# brakeBoard.net
KiCad netlist of a schematic drawn in EAGLE
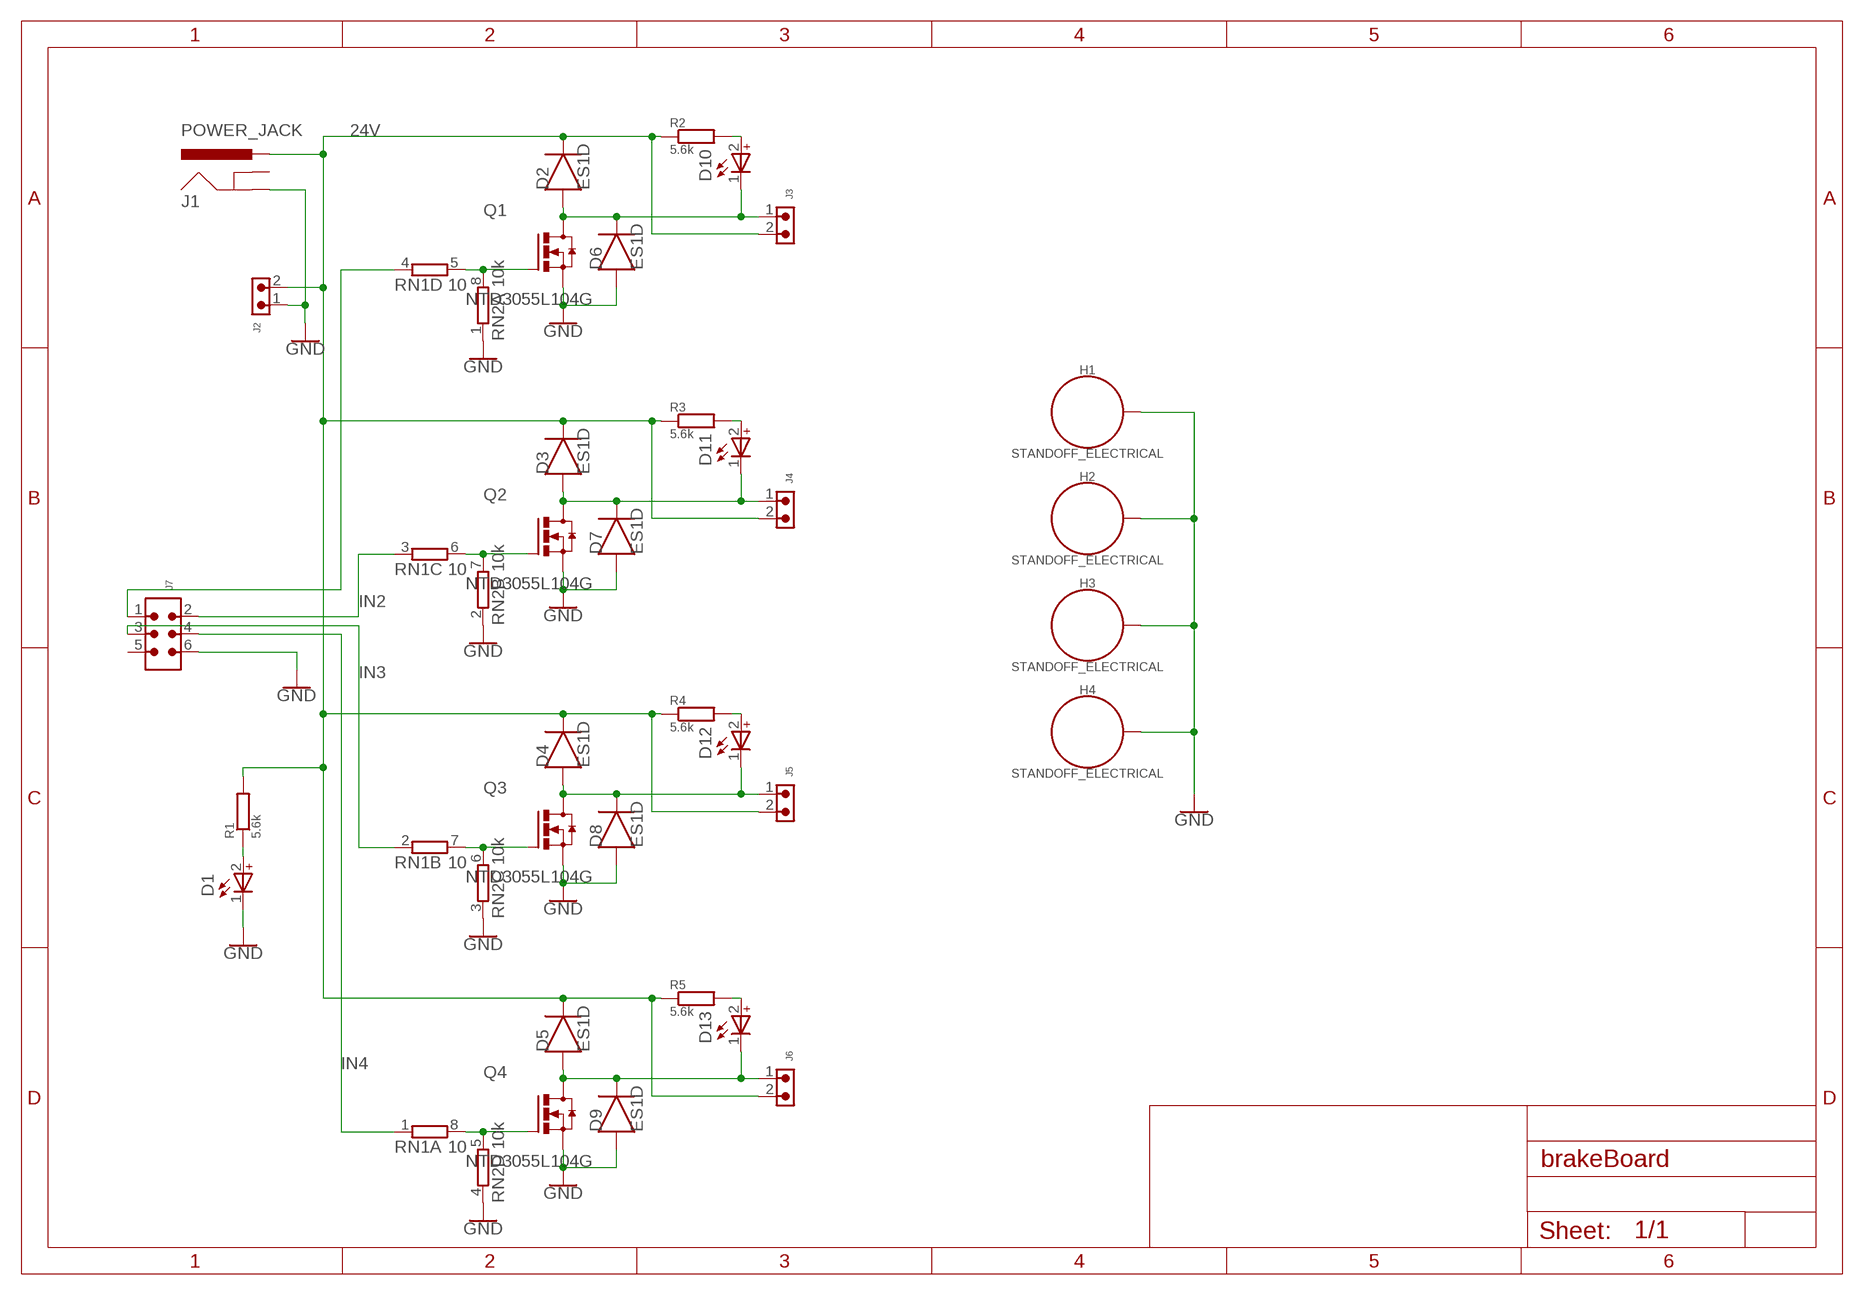
[diagram p0: schematic, sheet 1]

(export (version "E")
  (design (tool "Eeschema 10.0.6"))
  (components
    (comp (ref "D1")
      (value "WL-SMCD_0603_150060GS55040")
      (footprint "eagle-import:WL-SMCD_0603")
      (libsource (lib "eagle-import") (part "WL-SMCD_0603_150060GS55040"))
    )
    (comp (ref "D2")
      (value "ES1D")
      (footprint "eagle-import:DIOM5226X290N")
      (fields (field (name "MANUFACTURER") "ON Semiconductor "))
      (libsource (lib "eagle-import") (part "DIODE__SMAES1D"))
    )
    (comp (ref "D3")
      (value "ES1D")
      (footprint "eagle-import:DIOM5226X290N")
      (fields (field (name "MANUFACTURER") "ON Semiconductor "))
      (libsource (lib "eagle-import") (part "DIODE__SMAES1D"))
    )
    (comp (ref "D4")
      (value "ES1D")
      (footprint "eagle-import:DIOM5226X290N")
      (fields (field (name "MANUFACTURER") "ON Semiconductor "))
      (libsource (lib "eagle-import") (part "DIODE__SMAES1D"))
    )
    (comp (ref "D5")
      (value "ES1D")
      (footprint "eagle-import:DIOM5226X290N")
      (fields (field (name "MANUFACTURER") "ON Semiconductor "))
      (libsource (lib "eagle-import") (part "DIODE__SMAES1D"))
    )
    (comp (ref "D6")
      (value "ES1D")
      (footprint "eagle-import:DIOM5226X290N")
      (fields (field (name "MANUFACTURER") "ON Semiconductor "))
      (libsource (lib "eagle-import") (part "DIODE__SMAES1D"))
    )
    (comp (ref "D7")
      (value "ES1D")
      (footprint "eagle-import:DIOM5226X290N")
      (fields (field (name "MANUFACTURER") "ON Semiconductor "))
      (libsource (lib "eagle-import") (part "DIODE__SMAES1D"))
    )
    (comp (ref "D8")
      (value "ES1D")
      (footprint "eagle-import:DIOM5226X290N")
      (fields (field (name "MANUFACTURER") "ON Semiconductor "))
      (libsource (lib "eagle-import") (part "DIODE__SMAES1D"))
    )
    (comp (ref "D9")
      (value "ES1D")
      (footprint "eagle-import:DIOM5226X290N")
      (fields (field (name "MANUFACTURER") "ON Semiconductor "))
      (libsource (lib "eagle-import") (part "DIODE__SMAES1D"))
    )
    (comp (ref "D10")
      (value "WL-SMCD_0603_150060GS55040")
      (footprint "eagle-import:WL-SMCD_0603")
      (libsource (lib "eagle-import") (part "WL-SMCD_0603_150060GS55040"))
    )
    (comp (ref "D11")
      (value "WL-SMCD_0603_150060GS55040")
      (footprint "eagle-import:WL-SMCD_0603")
      (libsource (lib "eagle-import") (part "WL-SMCD_0603_150060GS55040"))
    )
    (comp (ref "D12")
      (value "WL-SMCD_0603_150060GS55040")
      (footprint "eagle-import:WL-SMCD_0603")
      (libsource (lib "eagle-import") (part "WL-SMCD_0603_150060GS55040"))
    )
    (comp (ref "D13")
      (value "WL-SMCD_0603_150060GS55040")
      (footprint "eagle-import:WL-SMCD_0603")
      (libsource (lib "eagle-import") (part "WL-SMCD_0603_150060GS55040"))
    )
    (comp (ref "H1")
      (value "STANDOFF_ELECTRICAL")
      (footprint "eagle-import:STANDOFF-ELECTRICAL")
      (libsource (lib "eagle-import") (part "STANDOFF_ELECTRICAL"))
    )
    (comp (ref "H2")
      (value "STANDOFF_ELECTRICAL")
      (footprint "eagle-import:STANDOFF-ELECTRICAL")
      (libsource (lib "eagle-import") (part "STANDOFF_ELECTRICAL"))
    )
    (comp (ref "H3")
      (value "STANDOFF_ELECTRICAL")
      (footprint "eagle-import:STANDOFF-ELECTRICAL")
      (libsource (lib "eagle-import") (part "STANDOFF_ELECTRICAL"))
    )
    (comp (ref "H4")
      (value "STANDOFF_ELECTRICAL")
      (footprint "eagle-import:STANDOFF-ELECTRICAL")
      (libsource (lib "eagle-import") (part "STANDOFF_ELECTRICAL"))
    )
    (comp (ref "J1")
      (value "POWER_JACK")
      (footprint "eagle-import:POWER_JACK_PTH")
      (libsource (lib "eagle-import") (part "POWER_JACK"))
    )
    (comp (ref "J2")
      (value "691322310002")
      (footprint "eagle-import:691322310002")
      (libsource (lib "eagle-import") (part "691322310002"))
    )
    (comp (ref "J3")
      (value "691321300002")
      (footprint "eagle-import:691321300002")
      (libsource (lib "eagle-import") (part "691321300002"))
    )
    (comp (ref "J4")
      (value "691321300002")
      (footprint "eagle-import:691321300002")
      (libsource (lib "eagle-import") (part "691321300002"))
    )
    (comp (ref "J5")
      (value "691321300002")
      (footprint "eagle-import:691321300002")
      (libsource (lib "eagle-import") (part "691321300002"))
    )
    (comp (ref "J6")
      (value "691321300002")
      (footprint "eagle-import:691321300002")
      (libsource (lib "eagle-import") (part "691321300002"))
    )
    (comp (ref "J7")
      (value "6120XX21621_61200621621")
      (footprint "eagle-import:61200621621")
      (libsource (lib "eagle-import") (part "6120XX21621_61200621621"))
    )
    (comp (ref "Q1")
      (value "NTD3055L104G")
      (footprint "eagle-import:DPAK3")
      (fields (field (name "MANUFACTURER") "ON SEMICONDUCTORS") (field (name "CREATED_BY") "PCBLayout.com"))
      (libsource (lib "eagle-import") (part "NTD3055L104G"))
    )
    (comp (ref "Q2")
      (value "NTD3055L104G")
      (footprint "eagle-import:DPAK3")
      (fields (field (name "MANUFACTURER") "ON SEMICONDUCTORS") (field (name "CREATED_BY") "PCBLayout.com"))
      (libsource (lib "eagle-import") (part "NTD3055L104G"))
    )
    (comp (ref "Q3")
      (value "NTD3055L104G")
      (footprint "eagle-import:DPAK3")
      (fields (field (name "MANUFACTURER") "ON SEMICONDUCTORS") (field (name "CREATED_BY") "PCBLayout.com"))
      (libsource (lib "eagle-import") (part "NTD3055L104G"))
    )
    (comp (ref "Q4")
      (value "NTD3055L104G")
      (footprint "eagle-import:DPAK3")
      (fields (field (name "MANUFACTURER") "ON SEMICONDUCTORS") (field (name "CREATED_BY") "PCBLayout.com"))
      (libsource (lib "eagle-import") (part "NTD3055L104G"))
    )
    (comp (ref "R1")
      (value "5.6k")
      (footprint "eagle-import:RESC2012X65")
      (libsource (lib "eagle-import") (part "RCHIP-0805(2012-METRIC)_"))
    )
    (comp (ref "R2")
      (value "5.6k")
      (footprint "eagle-import:RESC2012X65")
      (libsource (lib "eagle-import") (part "RCHIP-0805(2012-METRIC)_"))
    )
    (comp (ref "R3")
      (value "5.6k")
      (footprint "eagle-import:RESC2012X65")
      (libsource (lib "eagle-import") (part "RCHIP-0805(2012-METRIC)_"))
    )
    (comp (ref "R4")
      (value "5.6k")
      (footprint "eagle-import:RESC2012X65")
      (libsource (lib "eagle-import") (part "RCHIP-0805(2012-METRIC)_"))
    )
    (comp (ref "R5")
      (value "5.6k")
      (footprint "eagle-import:RESC2012X65")
      (libsource (lib "eagle-import") (part "RCHIP-0805(2012-METRIC)_"))
    )
    (comp (ref "RN1")
      (value "10")
      (footprint "eagle-import:CAY16_LONG_W")
      (libsource (lib "eagle-import") (part "4R-NCAY16_LONG_W"))
    )
    (comp (ref "RN2")
      (value "10k")
      (footprint "eagle-import:CAY16_LONG_W")
      (libsource (lib "eagle-import") (part "4R-NCAY16_LONG_W"))
    )
  )
  (nets
    (net (code "1") (name "/24V") (class "Default")
      (node (ref "D2") (pin "1") (pinfunction "C_1") (pintype "passive"))
      (node (ref "D3") (pin "1") (pinfunction "C_1") (pintype "passive"))
      (node (ref "D4") (pin "1") (pinfunction "C_1") (pintype "passive"))
      (node (ref "D5") (pin "1") (pinfunction "C_1") (pintype "passive"))
      (node (ref "J1") (pin "PWR") (pinfunction "PWR_PWR") (pintype "bidirectional"))
      (node (ref "J2") (pin "2") (pinfunction "2_2") (pintype "passive"))
      (node (ref "J3") (pin "2") (pinfunction "2_2") (pintype "passive"))
      (node (ref "J4") (pin "2") (pinfunction "2_2") (pintype "passive"))
      (node (ref "J5") (pin "2") (pinfunction "2_2") (pintype "passive"))
      (node (ref "J6") (pin "2") (pinfunction "2_2") (pintype "passive"))
      (node (ref "R1") (pin "2") (pinfunction "2_2") (pintype "passive"))
      (node (ref "R2") (pin "1") (pinfunction "1_1") (pintype "passive"))
      (node (ref "R3") (pin "1") (pinfunction "1_1") (pintype "passive"))
      (node (ref "R4") (pin "1") (pinfunction "1_1") (pintype "passive"))
      (node (ref "R5") (pin "1") (pinfunction "1_1") (pintype "passive"))
    )
    (net (code "2") (name "/IN2") (class "Default")
      (node (ref "J7") (pin "2") (pinfunction "2_2") (pintype "passive"))
      (node (ref "RN1") (pin "3") (pinfunction "1_3") (pintype "passive"))
    )
    (net (code "3") (name "/IN3") (class "Default")
      (node (ref "J7") (pin "3") (pinfunction "3_3") (pintype "passive"))
      (node (ref "RN1") (pin "2") (pinfunction "1_2") (pintype "passive"))
    )
    (net (code "4") (name "/IN4") (class "Default")
      (node (ref "J7") (pin "4") (pinfunction "4_4") (pintype "passive"))
      (node (ref "RN1") (pin "1") (pinfunction "1_1") (pintype "passive"))
    )
    (net (code "5") (name "GND") (class "Default")
      (node (ref "D1") (pin "1") (pinfunction "__1") (pintype "passive"))
      (node (ref "D6") (pin "2") (pinfunction "A_2") (pintype "passive"))
      (node (ref "D7") (pin "2") (pinfunction "A_2") (pintype "passive"))
      (node (ref "D8") (pin "2") (pinfunction "A_2") (pintype "passive"))
      (node (ref "D9") (pin "2") (pinfunction "A_2") (pintype "passive"))
      (node (ref "H1") (pin "P1") (pinfunction "P$1_P1") (pintype "bidirectional"))
      (node (ref "H2") (pin "P1") (pinfunction "P$1_P1") (pintype "bidirectional"))
      (node (ref "H3") (pin "P1") (pinfunction "P$1_P1") (pintype "bidirectional"))
      (node (ref "H4") (pin "P1") (pinfunction "P$1_P1") (pintype "bidirectional"))
      (node (ref "J1") (pin "GND") (pinfunction "GND_GND") (pintype "bidirectional"))
      (node (ref "J2") (pin "1") (pinfunction "1_1") (pintype "passive"))
      (node (ref "J7") (pin "6") (pinfunction "6_6") (pintype "passive"))
      (node (ref "Q1") (pin "2") (pinfunction "S_2") (pintype "passive"))
      (node (ref "Q2") (pin "2") (pinfunction "S_2") (pintype "passive"))
      (node (ref "Q3") (pin "2") (pinfunction "S_2") (pintype "passive"))
      (node (ref "Q4") (pin "2") (pinfunction "S_2") (pintype "passive"))
      (node (ref "RN2") (pin "1") (pinfunction "1_1") (pintype "passive"))
      (node (ref "RN2") (pin "2") (pinfunction "1_2") (pintype "passive"))
      (node (ref "RN2") (pin "3") (pinfunction "1_3") (pintype "passive"))
      (node (ref "RN2") (pin "4") (pinfunction "1_4") (pintype "passive"))
    )
    (net (code "6") (name "Net-(D1-+)") (class "Default")
      (node (ref "D1") (pin "2") (pinfunction "+_2") (pintype "passive"))
      (node (ref "R1") (pin "1") (pinfunction "1_1") (pintype "passive"))
    )
    (net (code "7") (name "Net-(D10-+)") (class "Default")
      (node (ref "D10") (pin "2") (pinfunction "+_2") (pintype "passive"))
      (node (ref "R2") (pin "2") (pinfunction "2_2") (pintype "passive"))
    )
    (net (code "8") (name "Net-(D10-_)") (class "Default")
      (node (ref "D10") (pin "1") (pinfunction "__1") (pintype "passive"))
      (node (ref "D2") (pin "2") (pinfunction "A_2") (pintype "passive"))
      (node (ref "D6") (pin "1") (pinfunction "C_1") (pintype "passive"))
      (node (ref "J3") (pin "1") (pinfunction "1_1") (pintype "passive"))
      (node (ref "Q1") (pin "3") (pinfunction "D_3") (pintype "passive"))
    )
    (net (code "9") (name "Net-(D11-+)") (class "Default")
      (node (ref "D11") (pin "2") (pinfunction "+_2") (pintype "passive"))
      (node (ref "R3") (pin "2") (pinfunction "2_2") (pintype "passive"))
    )
    (net (code "10") (name "Net-(D11-_)") (class "Default")
      (node (ref "D11") (pin "1") (pinfunction "__1") (pintype "passive"))
      (node (ref "D3") (pin "2") (pinfunction "A_2") (pintype "passive"))
      (node (ref "D7") (pin "1") (pinfunction "C_1") (pintype "passive"))
      (node (ref "J4") (pin "1") (pinfunction "1_1") (pintype "passive"))
      (node (ref "Q2") (pin "3") (pinfunction "D_3") (pintype "passive"))
    )
    (net (code "11") (name "Net-(D12-+)") (class "Default")
      (node (ref "D12") (pin "2") (pinfunction "+_2") (pintype "passive"))
      (node (ref "R4") (pin "2") (pinfunction "2_2") (pintype "passive"))
    )
    (net (code "12") (name "Net-(D12-_)") (class "Default")
      (node (ref "D12") (pin "1") (pinfunction "__1") (pintype "passive"))
      (node (ref "D4") (pin "2") (pinfunction "A_2") (pintype "passive"))
      (node (ref "D8") (pin "1") (pinfunction "C_1") (pintype "passive"))
      (node (ref "J5") (pin "1") (pinfunction "1_1") (pintype "passive"))
      (node (ref "Q3") (pin "3") (pinfunction "D_3") (pintype "passive"))
    )
    (net (code "13") (name "Net-(D13-+)") (class "Default")
      (node (ref "D13") (pin "2") (pinfunction "+_2") (pintype "passive"))
      (node (ref "R5") (pin "2") (pinfunction "2_2") (pintype "passive"))
    )
    (net (code "14") (name "Net-(D13-_)") (class "Default")
      (node (ref "D13") (pin "1") (pinfunction "__1") (pintype "passive"))
      (node (ref "D5") (pin "2") (pinfunction "A_2") (pintype "passive"))
      (node (ref "D9") (pin "1") (pinfunction "C_1") (pintype "passive"))
      (node (ref "J6") (pin "1") (pinfunction "1_1") (pintype "passive"))
      (node (ref "Q4") (pin "3") (pinfunction "D_3") (pintype "passive"))
    )
    (net (code "15") (name "Net-(Q1-G)") (class "Default")
      (node (ref "Q1") (pin "1") (pinfunction "G_1") (pintype "passive"))
      (node (ref "RN1") (pin "5") (pinfunction "2_5") (pintype "passive"))
      (node (ref "RN2") (pin "8") (pinfunction "2_8") (pintype "passive"))
    )
    (net (code "16") (name "Net-(Q2-G)") (class "Default")
      (node (ref "Q2") (pin "1") (pinfunction "G_1") (pintype "passive"))
      (node (ref "RN1") (pin "6") (pinfunction "2_6") (pintype "passive"))
      (node (ref "RN2") (pin "7") (pinfunction "2_7") (pintype "passive"))
    )
    (net (code "17") (name "Net-(Q3-G)") (class "Default")
      (node (ref "Q3") (pin "1") (pinfunction "G_1") (pintype "passive"))
      (node (ref "RN1") (pin "7") (pinfunction "2_7") (pintype "passive"))
      (node (ref "RN2") (pin "6") (pinfunction "2_6") (pintype "passive"))
    )
    (net (code "18") (name "Net-(Q4-G)") (class "Default")
      (node (ref "Q4") (pin "1") (pinfunction "G_1") (pintype "passive"))
      (node (ref "RN1") (pin "8") (pinfunction "2_8") (pintype "passive"))
      (node (ref "RN2") (pin "5") (pinfunction "2_5") (pintype "passive"))
    )
    (net (code "19") (name "Net-(RN1D-1)") (class "Default")
      (node (ref "J7") (pin "1") (pinfunction "1_1") (pintype "passive"))
      (node (ref "RN1") (pin "4") (pinfunction "1_4") (pintype "passive"))
    )
    (net (code "20") (name "unconnected-(J1-PadGNDBREAK)") (class "Default")
      (node (ref "J1") (pin "GNDBREAK") (pinfunction "GNDBREAK_GNDBREAK") (pintype "bidirectional"))
    )
    (net (code "21") (name "unconnected-(J7-Pad5)") (class "Default")
      (node (ref "J7") (pin "5") (pinfunction "5_5") (pintype "passive"))
    )
  )
)
